# CAN_node_analog.net
KiCad netlist of a schematic drawn in EAGLE
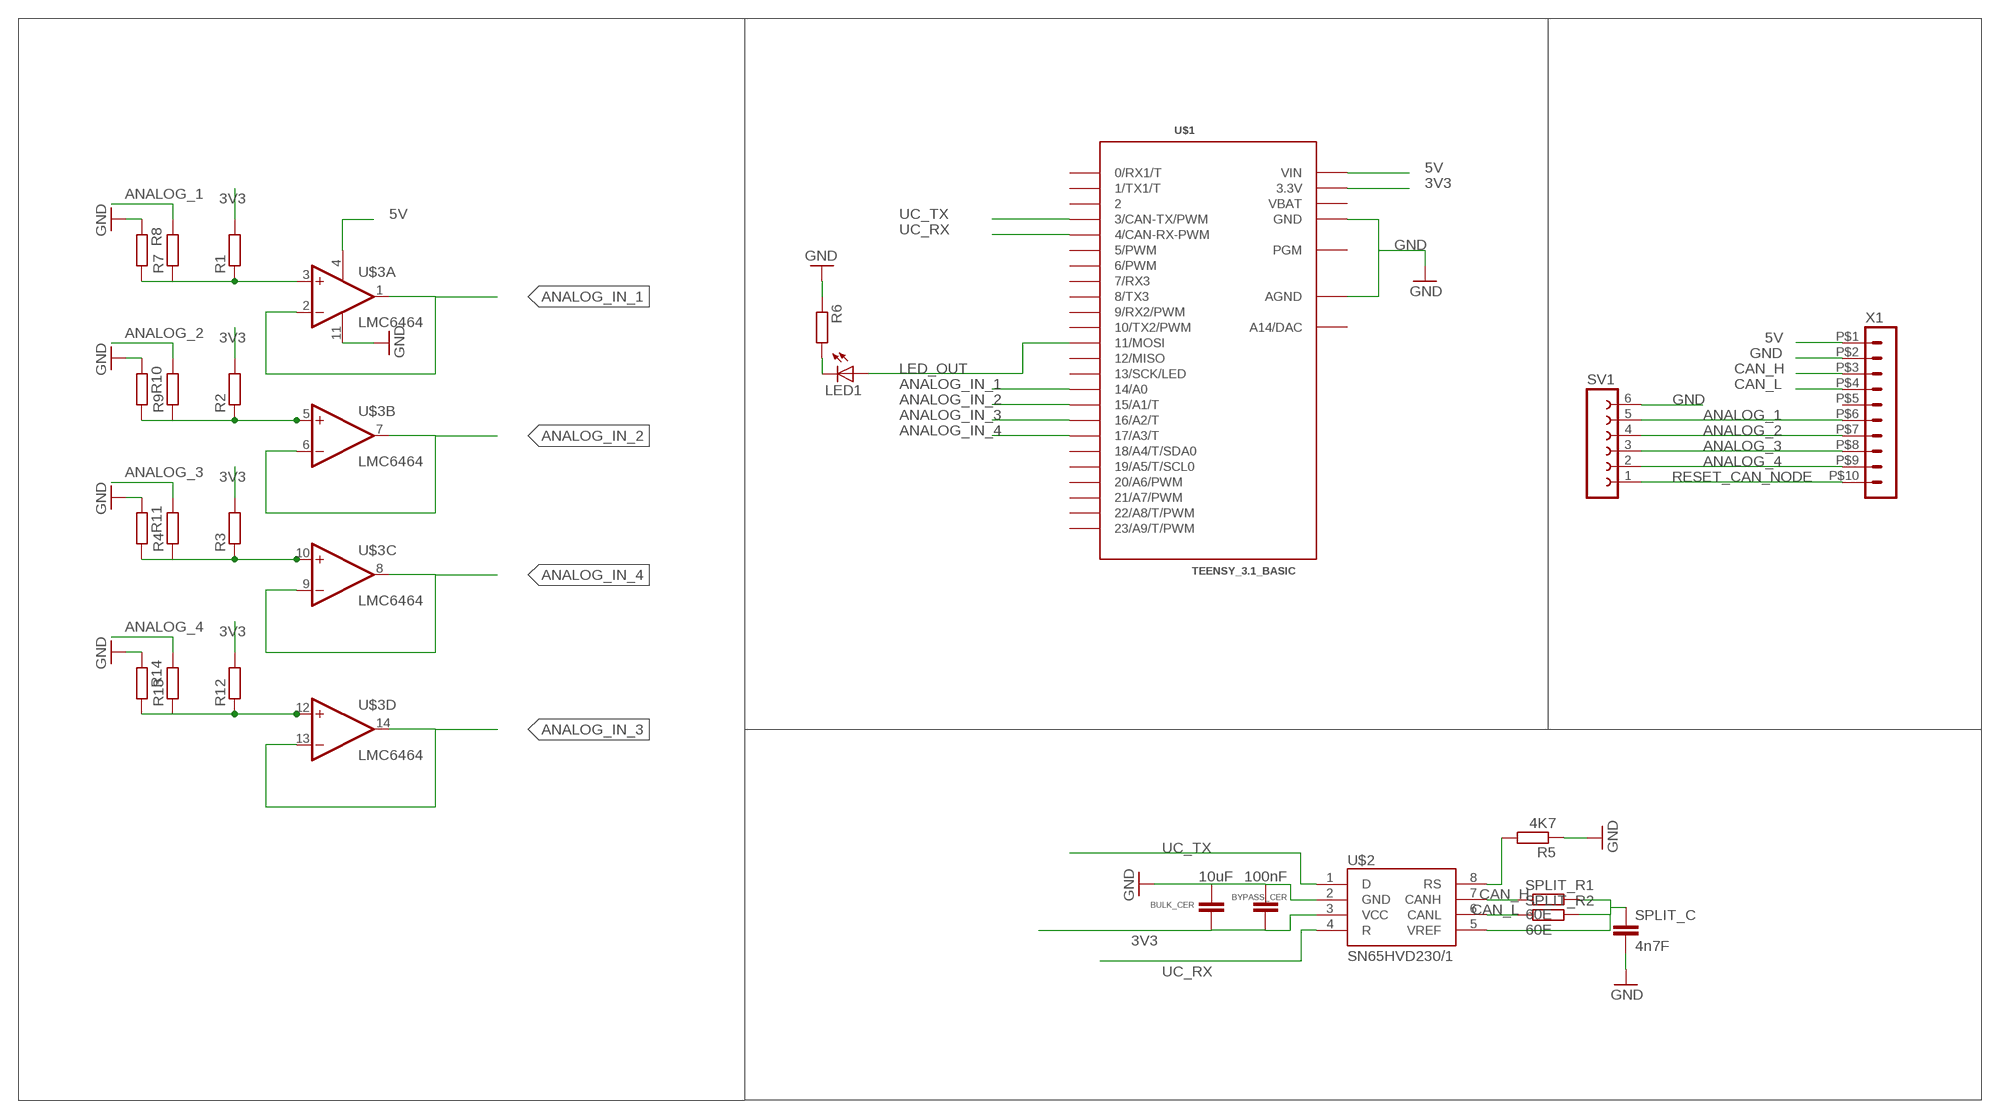
[diagram p0: schematic, sheet 1]

(export (version "E")
  (design (tool "Eeschema 10.0.6"))
  (components
    (comp (ref "BULK_CER")
      (value "10uF")
      (footprint "eagle-import:C0805")
      (libsource (lib "eagle-import") (part "C-EUC0805"))
    )
    (comp (ref "BYPASS_CER")
      (value "100nF")
      (footprint "eagle-import:C0805")
      (libsource (lib "eagle-import") (part "C-EUC0805"))
    )
    (comp (ref "LED1")
      (value "LED1206")
      (footprint "eagle-import:LED-1206")
      (libsource (lib "eagle-import") (part "LED1206"))
    )
    (comp (ref "R1")
      (value "R-EU_R0805")
      (footprint "eagle-import:R0805")
      (libsource (lib "eagle-import") (part "R-EU_R0805"))
    )
    (comp (ref "R2")
      (value "R-EU_R0805")
      (footprint "eagle-import:R0805")
      (libsource (lib "eagle-import") (part "R-EU_R0805"))
    )
    (comp (ref "R3")
      (value "R-EU_R0805")
      (footprint "eagle-import:R0805")
      (libsource (lib "eagle-import") (part "R-EU_R0805"))
    )
    (comp (ref "R4")
      (value "R-EU_R0805")
      (footprint "eagle-import:R0805")
      (libsource (lib "eagle-import") (part "R-EU_R0805"))
    )
    (comp (ref "R5")
      (value "4K7")
      (footprint "eagle-import:R0805")
      (libsource (lib "eagle-import") (part "LV_R-EU_R0805"))
    )
    (comp (ref "R6")
      (value "R-EU_R0805")
      (footprint "eagle-import:R0805")
      (libsource (lib "eagle-import") (part "R-EU_R0805"))
    )
    (comp (ref "R7")
      (value "R-EU_R0805")
      (footprint "eagle-import:R0805")
      (libsource (lib "eagle-import") (part "R-EU_R0805"))
    )
    (comp (ref "R8")
      (value "R-EU_R0805")
      (footprint "eagle-import:R0805")
      (libsource (lib "eagle-import") (part "R-EU_R0805"))
    )
    (comp (ref "R9")
      (value "R-EU_R0805")
      (footprint "eagle-import:R0805")
      (libsource (lib "eagle-import") (part "R-EU_R0805"))
    )
    (comp (ref "R10")
      (value "R-EU_R0805")
      (footprint "eagle-import:R0805")
      (libsource (lib "eagle-import") (part "R-EU_R0805"))
    )
    (comp (ref "R11")
      (value "R-EU_R0805")
      (footprint "eagle-import:R0805")
      (libsource (lib "eagle-import") (part "R-EU_R0805"))
    )
    (comp (ref "R12")
      (value "R-EU_R0805")
      (footprint "eagle-import:R0805")
      (libsource (lib "eagle-import") (part "R-EU_R0805"))
    )
    (comp (ref "R13")
      (value "R-EU_R0805")
      (footprint "eagle-import:R0805")
      (libsource (lib "eagle-import") (part "R-EU_R0805"))
    )
    (comp (ref "R14")
      (value "R-EU_R0805")
      (footprint "eagle-import:R0805")
      (libsource (lib "eagle-import") (part "R-EU_R0805"))
    )
    (comp (ref "SPLIT_C")
      (value "4n7F")
      (footprint "eagle-import:C0805")
      (libsource (lib "eagle-import") (part "C-EUC0805"))
    )
    (comp (ref "SPLIT_R1")
      (value "60E")
      (footprint "eagle-import:R0805")
      (libsource (lib "eagle-import") (part "LV_R-EU_R0805"))
    )
    (comp (ref "SPLIT_R2")
      (value "60E")
      (footprint "eagle-import:R0805")
      (libsource (lib "eagle-import") (part "LV_R-EU_R0805"))
    )
    (comp (ref "SV1")
      (value "FE06-1")
      (footprint "eagle-import:FE06")
      (libsource (lib "eagle-import") (part "FE06-1"))
    )
    (comp (ref "U$1")
      (value "TEENSY_3.1_BASIC")
      (footprint "eagle-import:TEENSY_3.1_BASIC")
      (libsource (lib "eagle-import") (part "TEENSY_3.1_BASIC"))
    )
    (comp (ref "U$2")
      (value "SN65HVD230/1")
      (footprint "eagle-import:SO8")
      (libsource (lib "eagle-import") (part "SN65HVD230/1"))
    )
    (comp (ref "U$3")
      (value "LMC6464")
      (footprint "eagle-import:SO14_LONGPADS")
      (libsource (lib "eagle-import") (part "LMC6464"))
    )
    (comp (ref "X1")
      (value "HEADER_POS10_43045-1012")
      (footprint "eagle-import:43045-1012")
      (libsource (lib "eagle-import") (part "HEADER_POS10_?43045-1012"))
    )
  )
  (nets
    (net (code "1") (name "/3V3") (class "Default")
      (node (ref "BULK_CER") (pin "1") (pinfunction "1_1") (pintype "passive"))
      (node (ref "BYPASS_CER") (pin "1") (pinfunction "1_1") (pintype "passive"))
      (node (ref "R1") (pin "2") (pinfunction "2_2") (pintype "passive"))
      (node (ref "R12") (pin "2") (pinfunction "2_2") (pintype "passive"))
      (node (ref "R2") (pin "2") (pinfunction "2_2") (pintype "passive"))
      (node (ref "R3") (pin "2") (pinfunction "2_2") (pintype "passive"))
      (node (ref "U$1") (pin "3.3V") (pinfunction "3.3V_3.3V") (pintype "power_in"))
      (node (ref "U$1") (pin "3.3V1") (pinfunction "3.3V_3.3V1") (pintype "power_in"))
      (node (ref "U$2") (pin "3") (pinfunction "VCC_3") (pintype "power_in"))
    )
    (net (code "2") (name "/5V") (class "Default")
      (node (ref "U$1") (pin "VIN") (pinfunction "VIN_VIN") (pintype "power_in"))
      (node (ref "U$3") (pin "4") (pinfunction "V+_4") (pintype "power_in"))
      (node (ref "X1") (pin "P$1") (pinfunction "1_P$1") (pintype "passive"))
    )
    (net (code "3") (name "/ANALOG_1") (class "Default")
      (node (ref "R7") (pin "2") (pinfunction "2_2") (pintype "passive"))
      (node (ref "SV1") (pin "5") (pinfunction "5_5") (pintype "passive"))
      (node (ref "X1") (pin "P$6") (pinfunction "6_P$6") (pintype "passive"))
    )
    (net (code "4") (name "/ANALOG_2") (class "Default")
      (node (ref "R9") (pin "2") (pinfunction "2_2") (pintype "passive"))
      (node (ref "SV1") (pin "4") (pinfunction "4_4") (pintype "passive"))
      (node (ref "X1") (pin "P$7") (pinfunction "7_P$7") (pintype "passive"))
    )
    (net (code "5") (name "/ANALOG_3") (class "Default")
      (node (ref "R4") (pin "2") (pinfunction "2_2") (pintype "passive"))
      (node (ref "SV1") (pin "3") (pinfunction "3_3") (pintype "passive"))
      (node (ref "X1") (pin "P$8") (pinfunction "8_P$8") (pintype "passive"))
    )
    (net (code "6") (name "/ANALOG_4") (class "Default")
      (node (ref "R13") (pin "2") (pinfunction "2_2") (pintype "passive"))
      (node (ref "SV1") (pin "2") (pinfunction "2_2") (pintype "passive"))
      (node (ref "X1") (pin "P$9") (pinfunction "9_P$9") (pintype "passive"))
    )
    (net (code "7") (name "/CAN_H") (class "Default")
      (node (ref "SPLIT_R1") (pin "1") (pinfunction "1_1") (pintype "passive"))
      (node (ref "U$2") (pin "7") (pinfunction "CANH_7") (pintype "bidirectional"))
      (node (ref "X1") (pin "P$3") (pinfunction "3_P$3") (pintype "passive"))
    )
    (net (code "8") (name "/CAN_L") (class "Default")
      (node (ref "SPLIT_R2") (pin "1") (pinfunction "1_1") (pintype "passive"))
      (node (ref "U$2") (pin "6") (pinfunction "CANL_6") (pintype "bidirectional"))
      (node (ref "X1") (pin "P$4") (pinfunction "4_P$4") (pintype "passive"))
    )
    (net (code "9") (name "/LED_OUT") (class "Default")
      (node (ref "LED1") (pin "A") (pinfunction "A_A") (pintype "passive"))
      (node (ref "U$1") (pin "11") (pinfunction "11/MOSI_11") (pintype "bidirectional"))
    )
    (net (code "10") (name "/RESET_CAN_NODE") (class "Default")
      (node (ref "SV1") (pin "1") (pinfunction "1_1") (pintype "passive"))
      (node (ref "X1") (pin "P$10") (pinfunction "10_P$10") (pintype "passive"))
    )
    (net (code "11") (name "/UC_RX") (class "Default")
      (node (ref "U$1") (pin "4") (pinfunction "4/CAN-RX-PWM_4") (pintype "bidirectional"))
      (node (ref "U$2") (pin "4") (pinfunction "R_4") (pintype "bidirectional"))
    )
    (net (code "12") (name "/UC_TX") (class "Default")
      (node (ref "U$1") (pin "3") (pinfunction "3/CAN-TX/PWM_3") (pintype "bidirectional"))
      (node (ref "U$2") (pin "1") (pinfunction "D_1") (pintype "bidirectional"))
    )
    (net (code "13") (name "/VBAT") (class "Default")
      (node (ref "U$1") (pin "VBAT") (pinfunction "VBAT_VBAT") (pintype "power_in"))
    )
    (net (code "14") (name "ANALOG_IN_1") (class "Default")
      (node (ref "U$1") (pin "14/A0") (pinfunction "14/A0_14/A0") (pintype "bidirectional"))
      (node (ref "U$3") (pin "1") (pinfunction "OUT_1") (pintype "output"))
      (node (ref "U$3") (pin "2") (pinfunction "-IN_2") (pintype "input"))
    )
    (net (code "15") (name "ANALOG_IN_2") (class "Default")
      (node (ref "U$1") (pin "15/A1") (pinfunction "15/A1/T_15/A1") (pintype "bidirectional"))
      (node (ref "U$3") (pin "6") (pinfunction "-IN_6") (pintype "input"))
      (node (ref "U$3") (pin "7") (pinfunction "OUT_7") (pintype "output"))
    )
    (net (code "16") (name "ANALOG_IN_3") (class "Default")
      (node (ref "U$1") (pin "16/A2") (pinfunction "16/A2/T_16/A2") (pintype "bidirectional"))
      (node (ref "U$3") (pin "13") (pinfunction "-IN_13") (pintype "input"))
      (node (ref "U$3") (pin "14") (pinfunction "OUT_14") (pintype "output"))
    )
    (net (code "17") (name "ANALOG_IN_4") (class "Default")
      (node (ref "U$1") (pin "17/A3") (pinfunction "17/A3/T_17/A3") (pintype "bidirectional"))
      (node (ref "U$3") (pin "8") (pinfunction "OUT_8") (pintype "output"))
      (node (ref "U$3") (pin "9") (pinfunction "-IN_9") (pintype "input"))
    )
    (net (code "18") (name "GND") (class "Default")
      (node (ref "BULK_CER") (pin "2") (pinfunction "2_2") (pintype "passive"))
      (node (ref "BYPASS_CER") (pin "2") (pinfunction "2_2") (pintype "passive"))
      (node (ref "R10") (pin "1") (pinfunction "1_1") (pintype "passive"))
      (node (ref "R11") (pin "1") (pinfunction "1_1") (pintype "passive"))
      (node (ref "R14") (pin "1") (pinfunction "1_1") (pintype "passive"))
      (node (ref "R5") (pin "1") (pinfunction "1_1") (pintype "passive"))
      (node (ref "R6") (pin "1") (pinfunction "1_1") (pintype "passive"))
      (node (ref "R8") (pin "1") (pinfunction "1_1") (pintype "passive"))
      (node (ref "SPLIT_C") (pin "2") (pinfunction "2_2") (pintype "passive"))
      (node (ref "SV1") (pin "6") (pinfunction "6_6") (pintype "passive"))
      (node (ref "U$1") (pin "AGND") (pinfunction "AGND_AGND") (pintype "power_in"))
      (node (ref "U$1") (pin "GND") (pinfunction "GND_GND") (pintype "power_in"))
      (node (ref "U$1") (pin "GND1") (pinfunction "GND_GND1") (pintype "power_in"))
      (node (ref "U$2") (pin "2") (pinfunction "GND_2") (pintype "power_in"))
      (node (ref "U$3") (pin "11") (pinfunction "V-_11") (pintype "power_in"))
      (node (ref "X1") (pin "P$2") (pinfunction "2_P$2") (pintype "passive"))
    )
    (net (code "19") (name "Net-(LED1-PadC)") (class "Default")
      (node (ref "LED1") (pin "C") (pinfunction "C_C") (pintype "passive"))
      (node (ref "R6") (pin "2") (pinfunction "2_2") (pintype "passive"))
    )
    (net (code "20") (name "Net-(U$2-RS)") (class "Default")
      (node (ref "R5") (pin "2") (pinfunction "2_2") (pintype "passive"))
      (node (ref "U$2") (pin "8") (pinfunction "RS_8") (pintype "bidirectional"))
    )
    (net (code "21") (name "Net-(U$2-VREF)") (class "Default")
      (node (ref "SPLIT_C") (pin "1") (pinfunction "1_1") (pintype "passive"))
      (node (ref "SPLIT_R1") (pin "2") (pinfunction "2_2") (pintype "passive"))
      (node (ref "SPLIT_R2") (pin "2") (pinfunction "2_2") (pintype "passive"))
      (node (ref "U$2") (pin "5") (pinfunction "VREF_5") (pintype "bidirectional"))
    )
    (net (code "22") (name "Net-(U$3A-+IN)") (class "Default")
      (node (ref "R1") (pin "1") (pinfunction "1_1") (pintype "passive"))
      (node (ref "R7") (pin "1") (pinfunction "1_1") (pintype "passive"))
      (node (ref "R8") (pin "2") (pinfunction "2_2") (pintype "passive"))
      (node (ref "U$3") (pin "3") (pinfunction "+IN_3") (pintype "input"))
    )
    (net (code "23") (name "Net-(U$3B-+IN)") (class "Default")
      (node (ref "R10") (pin "2") (pinfunction "2_2") (pintype "passive"))
      (node (ref "R2") (pin "1") (pinfunction "1_1") (pintype "passive"))
      (node (ref "R9") (pin "1") (pinfunction "1_1") (pintype "passive"))
      (node (ref "U$3") (pin "5") (pinfunction "+IN_5") (pintype "input"))
    )
    (net (code "24") (name "Net-(U$3C-+IN)") (class "Default")
      (node (ref "R11") (pin "2") (pinfunction "2_2") (pintype "passive"))
      (node (ref "R3") (pin "1") (pinfunction "1_1") (pintype "passive"))
      (node (ref "R4") (pin "1") (pinfunction "1_1") (pintype "passive"))
      (node (ref "U$3") (pin "10") (pinfunction "+IN_10") (pintype "input"))
    )
    (net (code "25") (name "Net-(U$3D-+IN)") (class "Default")
      (node (ref "R12") (pin "1") (pinfunction "1_1") (pintype "passive"))
      (node (ref "R13") (pin "1") (pinfunction "1_1") (pintype "passive"))
      (node (ref "R14") (pin "2") (pinfunction "2_2") (pintype "passive"))
      (node (ref "U$3") (pin "12") (pinfunction "+IN_12") (pintype "input"))
    )
    (net (code "26") (name "unconnected-(U$1-0{slash}RX1{slash}T-Pad0)") (class "Default")
      (node (ref "U$1") (pin "0") (pinfunction "0/RX1/T_0") (pintype "bidirectional"))
    )
    (net (code "27") (name "unconnected-(U$1-1{slash}TX1{slash}T-Pad1)") (class "Default")
      (node (ref "U$1") (pin "1") (pinfunction "1/TX1/T_1") (pintype "bidirectional"))
    )
    (net (code "28") (name "unconnected-(U$1-5{slash}PWM-Pad5)") (class "Default")
      (node (ref "U$1") (pin "5") (pinfunction "5/PWM_5") (pintype "bidirectional"))
    )
    (net (code "29") (name "unconnected-(U$1-6{slash}PWM-Pad6)") (class "Default")
      (node (ref "U$1") (pin "6") (pinfunction "6/PWM_6") (pintype "bidirectional"))
    )
    (net (code "30") (name "unconnected-(U$1-7{slash}RX3-Pad7)") (class "Default")
      (node (ref "U$1") (pin "7") (pinfunction "7/RX3_7") (pintype "bidirectional"))
    )
    (net (code "31") (name "unconnected-(U$1-8{slash}TX3-Pad8)") (class "Default")
      (node (ref "U$1") (pin "8") (pinfunction "8/TX3_8") (pintype "bidirectional"))
    )
    (net (code "32") (name "unconnected-(U$1-9{slash}RX2{slash}PWM-Pad9)") (class "Default")
      (node (ref "U$1") (pin "9") (pinfunction "9/RX2/PWM_9") (pintype "bidirectional"))
    )
    (net (code "33") (name "unconnected-(U$1-10{slash}TX2{slash}PWM-Pad10)") (class "Default")
      (node (ref "U$1") (pin "10") (pinfunction "10/TX2/PWM_10") (pintype "bidirectional"))
    )
    (net (code "34") (name "unconnected-(U$1-12{slash}MISO-Pad12)") (class "Default")
      (node (ref "U$1") (pin "12") (pinfunction "12/MISO_12") (pintype "bidirectional"))
    )
    (net (code "35") (name "unconnected-(U$1-13{slash}SCK{slash}LED-Pad13)") (class "Default")
      (node (ref "U$1") (pin "13") (pinfunction "13/SCK/LED_13") (pintype "bidirectional"))
    )
    (net (code "36") (name "unconnected-(U$1-18{slash}A4{slash}T{slash}SDA0-Pad18{slash}A4)") (class "Default")
      (node (ref "U$1") (pin "18/A4") (pinfunction "18/A4/T/SDA0_18/A4") (pintype "bidirectional"))
    )
    (net (code "37") (name "unconnected-(U$1-19{slash}A5{slash}T{slash}SCL0-Pad19{slash}A5)") (class "Default")
      (node (ref "U$1") (pin "19/A5") (pinfunction "19/A5/T/SCL0_19/A5") (pintype "bidirectional"))
    )
    (net (code "38") (name "unconnected-(U$1-20{slash}A6{slash}PWM-Pad20{slash}A6)") (class "Default")
      (node (ref "U$1") (pin "20/A6") (pinfunction "20/A6/PWM_20/A6") (pintype "bidirectional"))
    )
    (net (code "39") (name "unconnected-(U$1-21{slash}A7{slash}PWM-Pad21{slash}A7)") (class "Default")
      (node (ref "U$1") (pin "21/A7") (pinfunction "21/A7/PWM_21/A7") (pintype "bidirectional"))
    )
    (net (code "40") (name "unconnected-(U$1-22{slash}A8{slash}T{slash}PWM-Pad22{slash}A8)") (class "Default")
      (node (ref "U$1") (pin "22/A8") (pinfunction "22/A8/T/PWM_22/A8") (pintype "bidirectional"))
    )
    (net (code "41") (name "unconnected-(U$1-23{slash}A9{slash}T{slash}PWM-Pad23{slash}A9)") (class "Default")
      (node (ref "U$1") (pin "23/A9") (pinfunction "23/A9/T/PWM_23/A9") (pintype "bidirectional"))
    )
    (net (code "42") (name "unconnected-(U$1-A14{slash}DAC-PadA14)") (class "Default")
      (node (ref "U$1") (pin "A14") (pinfunction "A14/DAC_A14") (pintype "bidirectional"))
    )
    (net (code "43") (name "unconnected-(U$1-Pad2)") (class "Default")
      (node (ref "U$1") (pin "2") (pinfunction "2_2") (pintype "bidirectional"))
    )
    (net (code "44") (name "unconnected-(U$1-PadPGM)") (class "Default")
      (node (ref "U$1") (pin "PGM") (pinfunction "PGM_PGM") (pintype "bidirectional"))
    )
    (net (code "45") (name "unconnected-(X1-5-PadP$5)") (class "Default")
      (node (ref "X1") (pin "P$5") (pinfunction "5_P$5") (pintype "passive"))
    )
  )
)
